# mcu_energy.net
KiCad netlist of a schematic drawn in EAGLE
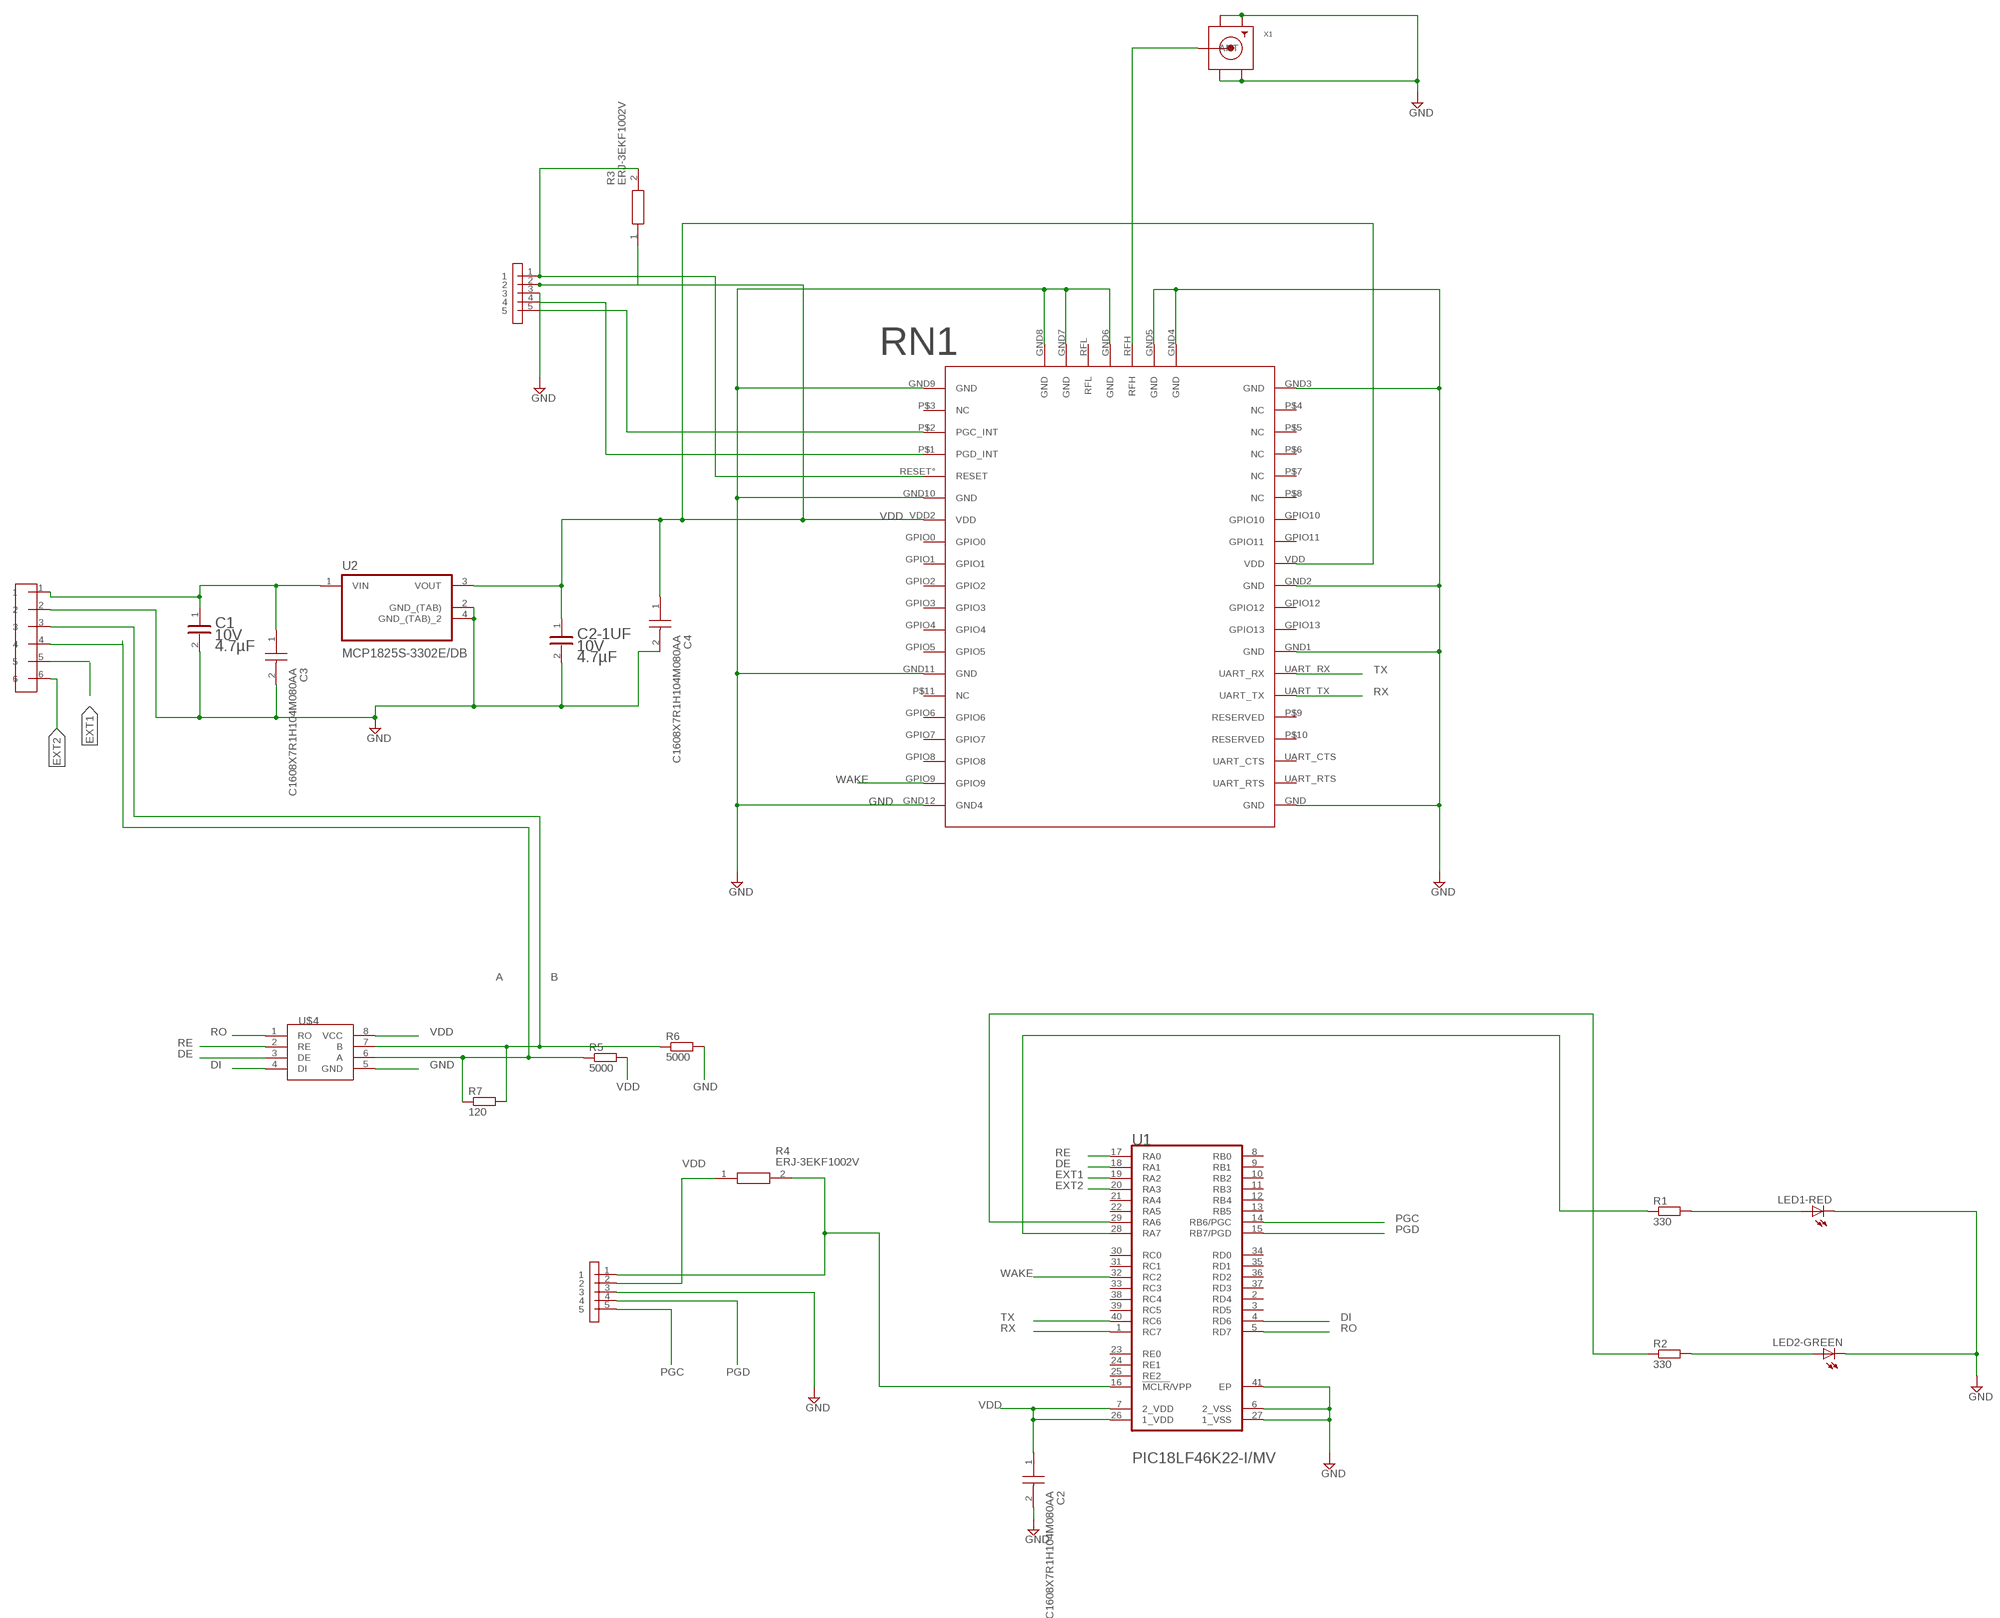
[diagram p0: schematic, sheet 1]

(export (version "E")
  (design (tool "Eeschema 10.0.6"))
  (components
    (comp (ref "C1")
      (value "KEMET_C0603C475K8PACTUKEMET_C0603C475K8PACTU_0_0")
      (footprint "eagle-import:KEMET_C0603C475K8PACTU_0")
      (fields
        (field (name "DIGIKEY_PART_NUMBER") "399-5503-1-ND")
        (field (name "MF") "Kemet")
        (field (name "MOUSER_PART_NUMBER") "80-C0603C475K8P")
      )
      (libsource (lib "eagle-import") (part "KEMET_C0603C475K8PACTUKEMET_C0603C475K8PACTU_0_0"))
    )
    (comp (ref "C2")
      (value "C1608X7R1H104M080AA")
      (footprint "eagle-import:CAPC1608X80N")
      (fields (field (name "MOUSER_PART_NUMBER") "810-C1608X7R1H104M"))
      (libsource (lib "eagle-import") (part "C1608X7R1H104M080AA"))
    )
    (comp (ref "C2-1UF")
      (value "KEMET_C0603C475K8PACTUKEMET_C0603C475K8PACTU_0_0")
      (footprint "eagle-import:KEMET_C0603C475K8PACTU_0")
      (fields
        (field (name "DIGIKEY_PART_NUMBER") "399-5503-1-ND")
        (field (name "MF") "Kemet")
        (field (name "MOUSER_PART_NUMBER") "80-C0603C475K8P")
      )
      (libsource (lib "eagle-import") (part "KEMET_C0603C475K8PACTUKEMET_C0603C475K8PACTU_0_0"))
    )
    (comp (ref "C3")
      (value "C1608X7R1H104M080AA")
      (footprint "eagle-import:CAPC1608X80N")
      (fields (field (name "MOUSER_PART_NUMBER") "810-C1608X7R1H104M"))
      (libsource (lib "eagle-import") (part "C1608X7R1H104M080AA"))
    )
    (comp (ref "C4")
      (value "C1608X7R1H104M080AA")
      (footprint "eagle-import:CAPC1608X80N")
      (fields (field (name "MOUSER_PART_NUMBER") "810-C1608X7R1H104M"))
      (libsource (lib "eagle-import") (part "C1608X7R1H104M080AA"))
    )
    (comp (ref "LED1-RED")
      (value "LEDCHIP-LED0603")
      (footprint "eagle-import:CHIP-LED0603")
      (libsource (lib "eagle-import") (part "LEDCHIP-LED0603"))
    )
    (comp (ref "LED2-GREEN")
      (value "LEDCHIP-LED0603")
      (footprint "eagle-import:CHIP-LED0603")
      (libsource (lib "eagle-import") (part "LEDCHIP-LED0603"))
    )
    (comp (ref "R1")
      (value "330")
      (footprint "eagle-import:R0603")
      (libsource (lib "eagle-import") (part "R-EU_R0603"))
    )
    (comp (ref "R2")
      (value "330")
      (footprint "eagle-import:R0603")
      (libsource (lib "eagle-import") (part "R-EU_R0603"))
    )
    (comp (ref "R3")
      (value "ERJ-3EKF1002V")
      (footprint "eagle-import:RESC1608X55N")
      (fields (field (name "MOUSER_PART_NUMBER") "667-ERJ-3EKF1002V"))
      (libsource (lib "eagle-import") (part "ERJ-3EKF1002V"))
    )
    (comp (ref "R4")
      (value "ERJ-3EKF1002V")
      (footprint "eagle-import:RESC1608X55N")
      (fields (field (name "MOUSER_PART_NUMBER") "667-ERJ-3EKF1002V"))
      (libsource (lib "eagle-import") (part "ERJ-3EKF1002V"))
    )
    (comp (ref "R5")
      (value "5000")
      (footprint "eagle-import:R0805")
      (libsource (lib "eagle-import") (part "rcl_334_R-EU_R0805"))
    )
    (comp (ref "R6")
      (value "5000")
      (footprint "eagle-import:R0805")
      (libsource (lib "eagle-import") (part "rcl_334_R-EU_R0805"))
    )
    (comp (ref "R7")
      (value "120")
      (footprint "eagle-import:R0805")
      (libsource (lib "eagle-import") (part "rcl_334_R-EU_R0805"))
    )
    (comp (ref "RN1")
      (value "NEW_RN2483")
      (footprint "eagle-import:NEW_RN2483")
      (libsource (lib "eagle-import") (part "NEW_RN2483"))
    )
    (comp (ref "U$1")
      (value "CONNECTOR62")
      (footprint "eagle-import:CONNECTOR6")
      (libsource (lib "eagle-import") (part "CONNECTOR62"))
    )
    (comp (ref "U$2")
      (value "ICSP52")
      (footprint "eagle-import:ICSP")
      (libsource (lib "eagle-import") (part "ICSP52"))
    )
    (comp (ref "U$3")
      (value "ICSP52")
      (footprint "eagle-import:ICSP")
      (libsource (lib "eagle-import") (part "ICSP52"))
    )
    (comp (ref "U$4")
      (value "AMD3485E")
      (footprint "eagle-import:AMD3485E")
      (libsource (lib "eagle-import") (part "AMD3485E"))
    )
    (comp (ref "U1")
      (value "MICROCHIP_PIC18LF46K22-I-MVMICROCHIP_PIC18LF46K22-I-MV_0_1")
      (footprint "eagle-import:MICROCHIP_PIC18LF46K22-I-MV_1")
      (fields (field (name "MF") "Microchip") (field (name "MPN") "PIC18LF46K22-I/MV"))
      (libsource (lib "eagle-import") (part "MICROCHIP_PIC18LF46K22-I-MVMICROCHIP_PIC18LF46K22-I-MV_0_1"))
    )
    (comp (ref "U2")
      (value "MCP1825S-3302E/DB")
      (footprint "eagle-import:SOT230P700X180-4N")
      (fields (field (name "MF") "Microchip"))
      (libsource (lib "eagle-import") (part "MCP1825S-3302E/DB"))
    )
    (comp (ref "X1")
      (value "SMACONNECTOR_EDGE")
      (footprint "eagle-import:SMA_EDGELAUNCH")
      (libsource (lib "eagle-import") (part "SMACONNECTOR_EDGE"))
    )
  )
  (nets
    (net (code "1") (name "/A") (class "Default")
      (node (ref "R5") (pin "1") (pinfunction "1_1") (pintype "passive"))
      (node (ref "R7") (pin "1") (pinfunction "1_1") (pintype "passive"))
      (node (ref "U$1") (pin "4") (pinfunction "4_4") (pintype "bidirectional"))
      (node (ref "U$4") (pin "6") (pinfunction "A_6") (pintype "bidirectional"))
    )
    (net (code "2") (name "/B") (class "Default")
      (node (ref "R6") (pin "1") (pinfunction "1_1") (pintype "passive"))
      (node (ref "R7") (pin "2") (pinfunction "2_2") (pintype "passive"))
      (node (ref "U$1") (pin "3") (pinfunction "3_3") (pintype "bidirectional"))
      (node (ref "U$4") (pin "7") (pinfunction "B_7") (pintype "bidirectional"))
    )
    (net (code "3") (name "/DE") (class "Default")
      (node (ref "U$4") (pin "3") (pinfunction "DE_3") (pintype "bidirectional"))
      (node (ref "U1") (pin "18") (pinfunction "RA1_18") (pintype "bidirectional"))
    )
    (net (code "4") (name "/DI") (class "Default")
      (node (ref "U$4") (pin "4") (pinfunction "DI_4") (pintype "bidirectional"))
      (node (ref "U1") (pin "4") (pinfunction "RD6_4") (pintype "bidirectional"))
    )
    (net (code "5") (name "/PGC") (class "Default")
      (node (ref "U$2") (pin "5") (pinfunction "5_5") (pintype "bidirectional"))
      (node (ref "U1") (pin "14") (pinfunction "RB6/PGC_14") (pintype "bidirectional"))
    )
    (net (code "6") (name "/PGD") (class "Default")
      (node (ref "U$2") (pin "4") (pinfunction "4_4") (pintype "bidirectional"))
      (node (ref "U1") (pin "15") (pinfunction "RB7/PGD_15") (pintype "bidirectional"))
    )
    (net (code "7") (name "/RE") (class "Default")
      (node (ref "U$4") (pin "2") (pinfunction "RE_2") (pintype "bidirectional"))
      (node (ref "U1") (pin "17") (pinfunction "RA0_17") (pintype "bidirectional"))
    )
    (net (code "8") (name "/RO") (class "Default")
      (node (ref "U$4") (pin "1") (pinfunction "RO_1") (pintype "bidirectional"))
      (node (ref "U1") (pin "5") (pinfunction "RD7_5") (pintype "bidirectional"))
    )
    (net (code "9") (name "/RX") (class "Default")
      (node (ref "RN1") (pin "UART_TX") (pinfunction "UART_TX_UART_TX") (pintype "bidirectional"))
      (node (ref "U1") (pin "1") (pinfunction "RC7_1") (pintype "bidirectional"))
    )
    (net (code "10") (name "/TX") (class "Default")
      (node (ref "RN1") (pin "UART_RX") (pinfunction "UART_RX_UART_RX") (pintype "bidirectional"))
      (node (ref "U1") (pin "40") (pinfunction "RC6_40") (pintype "bidirectional"))
    )
    (net (code "11") (name "/VDD") (class "Default")
      (node (ref "C2") (pin "1") (pinfunction "1_1") (pintype "bidirectional"))
      (node (ref "C2-1UF") (pin "1") (pinfunction "1_1") (pintype "bidirectional"))
      (node (ref "C4") (pin "1") (pinfunction "1_1") (pintype "bidirectional"))
      (node (ref "R3") (pin "1") (pinfunction "1_1") (pintype "bidirectional"))
      (node (ref "R4") (pin "1") (pinfunction "1_1") (pintype "bidirectional"))
      (node (ref "R5") (pin "2") (pinfunction "2_2") (pintype "passive"))
      (node (ref "RN1") (pin "VDD") (pinfunction "VDD_VDD") (pintype "bidirectional"))
      (node (ref "RN1") (pin "VDD2") (pinfunction "VDD_VDD2") (pintype "bidirectional"))
      (node (ref "U$2") (pin "2") (pinfunction "2_2") (pintype "bidirectional"))
      (node (ref "U$3") (pin "2") (pinfunction "2_2") (pintype "bidirectional"))
      (node (ref "U$4") (pin "8") (pinfunction "VCC_8") (pintype "bidirectional"))
      (node (ref "U1") (pin "26") (pinfunction "1_VDD_26") (pintype "power_in"))
      (node (ref "U1") (pin "7") (pinfunction "2_VDD_7") (pintype "power_in"))
      (node (ref "U2") (pin "3") (pinfunction "VOUT_3") (pintype "output"))
    )
    (net (code "12") (name "/WAKE") (class "Default")
      (node (ref "RN1") (pin "GPIO9") (pinfunction "GPIO9_GPIO9") (pintype "bidirectional"))
      (node (ref "U1") (pin "32") (pinfunction "RC2_32") (pintype "bidirectional"))
    )
    (net (code "13") (name "EXT1") (class "Default")
      (node (ref "U$1") (pin "5") (pinfunction "5_5") (pintype "bidirectional"))
      (node (ref "U1") (pin "19") (pinfunction "RA2_19") (pintype "bidirectional"))
    )
    (net (code "14") (name "EXT2") (class "Default")
      (node (ref "U$1") (pin "6") (pinfunction "6_6") (pintype "bidirectional"))
      (node (ref "U1") (pin "20") (pinfunction "RA3_20") (pintype "bidirectional"))
    )
    (net (code "15") (name "GND") (class "Default")
      (node (ref "C1") (pin "2") (pinfunction "2_2") (pintype "bidirectional"))
      (node (ref "C2") (pin "2") (pinfunction "2_2") (pintype "bidirectional"))
      (node (ref "C2-1UF") (pin "2") (pinfunction "2_2") (pintype "bidirectional"))
      (node (ref "C3") (pin "2") (pinfunction "2_2") (pintype "bidirectional"))
      (node (ref "C4") (pin "2") (pinfunction "2_2") (pintype "bidirectional"))
      (node (ref "LED1-RED") (pin "C") (pinfunction "C_C") (pintype "passive"))
      (node (ref "LED2-GREEN") (pin "C") (pinfunction "C_C") (pintype "passive"))
      (node (ref "R6") (pin "2") (pinfunction "2_2") (pintype "passive"))
      (node (ref "RN1") (pin "GND") (pinfunction "GND_GND") (pintype "bidirectional"))
      (node (ref "RN1") (pin "GND1") (pinfunction "GND_GND1") (pintype "bidirectional"))
      (node (ref "RN1") (pin "GND10") (pinfunction "GND_GND10") (pintype "bidirectional"))
      (node (ref "RN1") (pin "GND11") (pinfunction "GND_GND11") (pintype "bidirectional"))
      (node (ref "RN1") (pin "GND12") (pinfunction "GND4_GND12") (pintype "bidirectional"))
      (node (ref "RN1") (pin "GND2") (pinfunction "GND_GND2") (pintype "bidirectional"))
      (node (ref "RN1") (pin "GND3") (pinfunction "GND_GND3") (pintype "bidirectional"))
      (node (ref "RN1") (pin "GND4") (pinfunction "GND_GND4") (pintype "bidirectional"))
      (node (ref "RN1") (pin "GND5") (pinfunction "GND_GND5") (pintype "bidirectional"))
      (node (ref "RN1") (pin "GND6") (pinfunction "GND_GND6") (pintype "bidirectional"))
      (node (ref "RN1") (pin "GND7") (pinfunction "GND_GND7") (pintype "bidirectional"))
      (node (ref "RN1") (pin "GND8") (pinfunction "GND_GND8") (pintype "bidirectional"))
      (node (ref "RN1") (pin "GND9") (pinfunction "GND_GND9") (pintype "bidirectional"))
      (node (ref "U$1") (pin "2") (pinfunction "2_2") (pintype "bidirectional"))
      (node (ref "U$2") (pin "3") (pinfunction "3_3") (pintype "bidirectional"))
      (node (ref "U$3") (pin "3") (pinfunction "3_3") (pintype "bidirectional"))
      (node (ref "U$4") (pin "5") (pinfunction "GND_5") (pintype "bidirectional"))
      (node (ref "U1") (pin "27") (pinfunction "1_VSS_27") (pintype "power_in"))
      (node (ref "U1") (pin "41") (pinfunction "EP_41") (pintype "passive"))
      (node (ref "U1") (pin "6") (pinfunction "2_VSS_6") (pintype "power_in"))
      (node (ref "U2") (pin "2") (pinfunction "GND_(TAB)_2") (pintype "power_in"))
      (node (ref "U2") (pin "4") (pinfunction "GND_(TAB)_2_4") (pintype "power_in"))
      (node (ref "X1") (pin "GND@1") (pinfunction "GND4_GND@1") (pintype "power_in"))
      (node (ref "X1") (pin "GND@2") (pinfunction "GND3_GND@2") (pintype "power_in"))
      (node (ref "X1") (pin "GND@3") (pinfunction "GND2_GND@3") (pintype "power_in"))
      (node (ref "X1") (pin "GND@4") (pinfunction "GND1_GND@4") (pintype "power_in"))
    )
    (net (code "16") (name "Net-(LED1-RED-PadA)") (class "Default")
      (node (ref "LED1-RED") (pin "A") (pinfunction "A_A") (pintype "passive"))
      (node (ref "R1") (pin "2") (pinfunction "2_2") (pintype "passive"))
    )
    (net (code "17") (name "Net-(LED2-GREEN-PadA)") (class "Default")
      (node (ref "LED2-GREEN") (pin "A") (pinfunction "A_A") (pintype "passive"))
      (node (ref "R2") (pin "2") (pinfunction "2_2") (pintype "passive"))
    )
    (net (code "18") (name "Net-(RN1-PGC_INT)") (class "Default")
      (node (ref "RN1") (pin "P$2") (pinfunction "PGC_INT_P$2") (pintype "bidirectional"))
      (node (ref "U$3") (pin "5") (pinfunction "5_5") (pintype "bidirectional"))
    )
    (net (code "19") (name "Net-(RN1-PGD_INT)") (class "Default")
      (node (ref "RN1") (pin "P$1") (pinfunction "PGD_INT_P$1") (pintype "bidirectional"))
      (node (ref "U$3") (pin "4") (pinfunction "4_4") (pintype "bidirectional"))
    )
    (net (code "20") (name "Net-(RN1-RESET)") (class "Default")
      (node (ref "R3") (pin "2") (pinfunction "2_2") (pintype "bidirectional"))
      (node (ref "RN1") (pin "RESET°") (pinfunction "RESET_RESET°") (pintype "bidirectional"))
      (node (ref "U$3") (pin "1") (pinfunction "1_1") (pintype "bidirectional"))
    )
    (net (code "21") (name "Net-(U1-RA6)") (class "Default")
      (node (ref "R2") (pin "1") (pinfunction "1_1") (pintype "passive"))
      (node (ref "U1") (pin "29") (pinfunction "RA6_29") (pintype "bidirectional"))
    )
    (net (code "22") (name "Net-(U1-RA7)") (class "Default")
      (node (ref "R1") (pin "1") (pinfunction "1_1") (pintype "passive"))
      (node (ref "U1") (pin "28") (pinfunction "RA7_28") (pintype "bidirectional"))
    )
    (net (code "23") (name "Net-(U1-~{MCLR}{slash}VPP)") (class "Default")
      (node (ref "R4") (pin "2") (pinfunction "2_2") (pintype "bidirectional"))
      (node (ref "U$2") (pin "1") (pinfunction "1_1") (pintype "bidirectional"))
      (node (ref "U1") (pin "16") (pinfunction "~{MCLR}/VPP_16") (pintype "input"))
    )
    (net (code "24") (name "Net-(U2-VIN)") (class "Default")
      (node (ref "C1") (pin "1") (pinfunction "1_1") (pintype "bidirectional"))
      (node (ref "C3") (pin "1") (pinfunction "1_1") (pintype "bidirectional"))
      (node (ref "U$1") (pin "1") (pinfunction "1_1") (pintype "bidirectional"))
      (node (ref "U2") (pin "1") (pinfunction "VIN_1") (pintype "input"))
    )
    (net (code "25") (name "Net-(X1-ANT)") (class "Default")
      (node (ref "RN1") (pin "RFH") (pinfunction "RFH_RFH") (pintype "bidirectional"))
      (node (ref "X1") (pin "P") (pinfunction "ANT_P") (pintype "bidirectional"))
    )
    (net (code "26") (name "unconnected-(RN1-NC-PadP$3)") (class "Default")
      (node (ref "RN1") (pin "P$3") (pinfunction "NC_P$3") (pintype "bidirectional"))
    )
    (net (code "27") (name "unconnected-(RN1-NC-PadP$4)") (class "Default")
      (node (ref "RN1") (pin "P$4") (pinfunction "NC_P$4") (pintype "bidirectional"))
    )
    (net (code "28") (name "unconnected-(RN1-NC-PadP$5)") (class "Default")
      (node (ref "RN1") (pin "P$5") (pinfunction "NC_P$5") (pintype "bidirectional"))
    )
    (net (code "29") (name "unconnected-(RN1-NC-PadP$6)") (class "Default")
      (node (ref "RN1") (pin "P$6") (pinfunction "NC_P$6") (pintype "bidirectional"))
    )
    (net (code "30") (name "unconnected-(RN1-NC-PadP$7)") (class "Default")
      (node (ref "RN1") (pin "P$7") (pinfunction "NC_P$7") (pintype "bidirectional"))
    )
    (net (code "31") (name "unconnected-(RN1-NC-PadP$8)") (class "Default")
      (node (ref "RN1") (pin "P$8") (pinfunction "NC_P$8") (pintype "bidirectional"))
    )
    (net (code "32") (name "unconnected-(RN1-NC-PadP$11)") (class "Default")
      (node (ref "RN1") (pin "P$11") (pinfunction "NC_P$11") (pintype "bidirectional"))
    )
    (net (code "33") (name "unconnected-(RN1-PadGPIO0)") (class "Default")
      (node (ref "RN1") (pin "GPIO0") (pinfunction "GPIO0_GPIO0") (pintype "bidirectional"))
    )
    (net (code "34") (name "unconnected-(RN1-PadGPIO1)") (class "Default")
      (node (ref "RN1") (pin "GPIO1") (pinfunction "GPIO1_GPIO1") (pintype "bidirectional"))
    )
    (net (code "35") (name "unconnected-(RN1-PadGPIO2)") (class "Default")
      (node (ref "RN1") (pin "GPIO2") (pinfunction "GPIO2_GPIO2") (pintype "bidirectional"))
    )
    (net (code "36") (name "unconnected-(RN1-PadGPIO3)") (class "Default")
      (node (ref "RN1") (pin "GPIO3") (pinfunction "GPIO3_GPIO3") (pintype "bidirectional"))
    )
    (net (code "37") (name "unconnected-(RN1-PadGPIO4)") (class "Default")
      (node (ref "RN1") (pin "GPIO4") (pinfunction "GPIO4_GPIO4") (pintype "bidirectional"))
    )
    (net (code "38") (name "unconnected-(RN1-PadGPIO5)") (class "Default")
      (node (ref "RN1") (pin "GPIO5") (pinfunction "GPIO5_GPIO5") (pintype "bidirectional"))
    )
    (net (code "39") (name "unconnected-(RN1-PadGPIO6)") (class "Default")
      (node (ref "RN1") (pin "GPIO6") (pinfunction "GPIO6_GPIO6") (pintype "bidirectional"))
    )
    (net (code "40") (name "unconnected-(RN1-PadGPIO7)") (class "Default")
      (node (ref "RN1") (pin "GPIO7") (pinfunction "GPIO7_GPIO7") (pintype "bidirectional"))
    )
    (net (code "41") (name "unconnected-(RN1-PadGPIO8)") (class "Default")
      (node (ref "RN1") (pin "GPIO8") (pinfunction "GPIO8_GPIO8") (pintype "bidirectional"))
    )
    (net (code "42") (name "unconnected-(RN1-PadGPIO10)") (class "Default")
      (node (ref "RN1") (pin "GPIO10") (pinfunction "GPIO10_GPIO10") (pintype "bidirectional"))
    )
    (net (code "43") (name "unconnected-(RN1-PadGPIO11)") (class "Default")
      (node (ref "RN1") (pin "GPIO11") (pinfunction "GPIO11_GPIO11") (pintype "bidirectional"))
    )
    (net (code "44") (name "unconnected-(RN1-PadGPIO12)") (class "Default")
      (node (ref "RN1") (pin "GPIO12") (pinfunction "GPIO12_GPIO12") (pintype "bidirectional"))
    )
    (net (code "45") (name "unconnected-(RN1-PadGPIO13)") (class "Default")
      (node (ref "RN1") (pin "GPIO13") (pinfunction "GPIO13_GPIO13") (pintype "bidirectional"))
    )
    (net (code "46") (name "unconnected-(RN1-PadRFL)") (class "Default")
      (node (ref "RN1") (pin "RFL") (pinfunction "RFL_RFL") (pintype "bidirectional"))
    )
    (net (code "47") (name "unconnected-(RN1-PadUART_CTS)") (class "Default")
      (node (ref "RN1") (pin "UART_CTS") (pinfunction "UART_CTS_UART_CTS") (pintype "bidirectional"))
    )
    (net (code "48") (name "unconnected-(RN1-PadUART_RTS)") (class "Default")
      (node (ref "RN1") (pin "UART_RTS") (pinfunction "UART_RTS_UART_RTS") (pintype "bidirectional"))
    )
    (net (code "49") (name "unconnected-(RN1-RESERVED-PadP$9)") (class "Default")
      (node (ref "RN1") (pin "P$9") (pinfunction "RESERVED_P$9") (pintype "bidirectional"))
    )
    (net (code "50") (name "unconnected-(RN1-RESERVED-PadP$10)") (class "Default")
      (node (ref "RN1") (pin "P$10") (pinfunction "RESERVED_P$10") (pintype "bidirectional"))
    )
    (net (code "51") (name "unconnected-(U1-RA4-Pad21)") (class "Default")
      (node (ref "U1") (pin "21") (pinfunction "RA4_21") (pintype "bidirectional"))
    )
    (net (code "52") (name "unconnected-(U1-RA5-Pad22)") (class "Default")
      (node (ref "U1") (pin "22") (pinfunction "RA5_22") (pintype "bidirectional"))
    )
    (net (code "53") (name "unconnected-(U1-RB0-Pad8)") (class "Default")
      (node (ref "U1") (pin "8") (pinfunction "RB0_8") (pintype "bidirectional"))
    )
    (net (code "54") (name "unconnected-(U1-RB1-Pad9)") (class "Default")
      (node (ref "U1") (pin "9") (pinfunction "RB1_9") (pintype "bidirectional"))
    )
    (net (code "55") (name "unconnected-(U1-RB2-Pad10)") (class "Default")
      (node (ref "U1") (pin "10") (pinfunction "RB2_10") (pintype "bidirectional"))
    )
    (net (code "56") (name "unconnected-(U1-RB3-Pad11)") (class "Default")
      (node (ref "U1") (pin "11") (pinfunction "RB3_11") (pintype "bidirectional"))
    )
    (net (code "57") (name "unconnected-(U1-RB4-Pad12)") (class "Default")
      (node (ref "U1") (pin "12") (pinfunction "RB4_12") (pintype "bidirectional"))
    )
    (net (code "58") (name "unconnected-(U1-RB5-Pad13)") (class "Default")
      (node (ref "U1") (pin "13") (pinfunction "RB5_13") (pintype "bidirectional"))
    )
    (net (code "59") (name "unconnected-(U1-RC0-Pad30)") (class "Default")
      (node (ref "U1") (pin "30") (pinfunction "RC0_30") (pintype "bidirectional"))
    )
    (net (code "60") (name "unconnected-(U1-RC1-Pad31)") (class "Default")
      (node (ref "U1") (pin "31") (pinfunction "RC1_31") (pintype "bidirectional"))
    )
    (net (code "61") (name "unconnected-(U1-RC3-Pad33)") (class "Default")
      (node (ref "U1") (pin "33") (pinfunction "RC3_33") (pintype "bidirectional"))
    )
    (net (code "62") (name "unconnected-(U1-RC4-Pad38)") (class "Default")
      (node (ref "U1") (pin "38") (pinfunction "RC4_38") (pintype "bidirectional"))
    )
    (net (code "63") (name "unconnected-(U1-RC5-Pad39)") (class "Default")
      (node (ref "U1") (pin "39") (pinfunction "RC5_39") (pintype "bidirectional"))
    )
    (net (code "64") (name "unconnected-(U1-RD0-Pad34)") (class "Default")
      (node (ref "U1") (pin "34") (pinfunction "RD0_34") (pintype "bidirectional"))
    )
    (net (code "65") (name "unconnected-(U1-RD1-Pad35)") (class "Default")
      (node (ref "U1") (pin "35") (pinfunction "RD1_35") (pintype "bidirectional"))
    )
    (net (code "66") (name "unconnected-(U1-RD2-Pad36)") (class "Default")
      (node (ref "U1") (pin "36") (pinfunction "RD2_36") (pintype "bidirectional"))
    )
    (net (code "67") (name "unconnected-(U1-RD3-Pad37)") (class "Default")
      (node (ref "U1") (pin "37") (pinfunction "RD3_37") (pintype "bidirectional"))
    )
    (net (code "68") (name "unconnected-(U1-RD4-Pad2)") (class "Default")
      (node (ref "U1") (pin "2") (pinfunction "RD4_2") (pintype "bidirectional"))
    )
    (net (code "69") (name "unconnected-(U1-RD5-Pad3)") (class "Default")
      (node (ref "U1") (pin "3") (pinfunction "RD5_3") (pintype "bidirectional"))
    )
    (net (code "70") (name "unconnected-(U1-RE0-Pad23)") (class "Default")
      (node (ref "U1") (pin "23") (pinfunction "RE0_23") (pintype "bidirectional"))
    )
    (net (code "71") (name "unconnected-(U1-RE1-Pad24)") (class "Default")
      (node (ref "U1") (pin "24") (pinfunction "RE1_24") (pintype "bidirectional"))
    )
    (net (code "72") (name "unconnected-(U1-RE2-Pad25)") (class "Default")
      (node (ref "U1") (pin "25") (pinfunction "RE2_25") (pintype "bidirectional"))
    )
  )
)
